# Main.net
KiCad netlist of a schematic drawn in Altium Designer
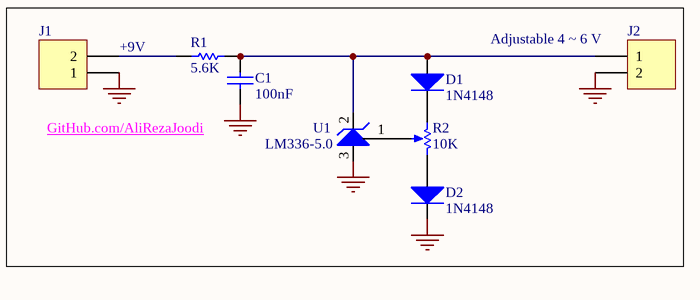
[diagram p0: Main.SchDoc]

(export (version "E")
  (design (tool "Eeschema 10.0.6"))
  (components
    (comp (ref "C1")
      (value "100nF")
      (footprint "CAPNTO2.54-3.05x1.78A")
      (description "Capacitor")
      (fields
        (field (name "MANUFACTURER") "Generic Components")
        (field (name "Comment") "Cap")
        (field (name "PUBLISHER") "Altium Limited")
      )
      (libsource (lib "Miscellaneous Devices") (part "Cap"))
    )
    (comp (ref "D1")
      (value "1N4148")
      (footprint "DIODE0.4_Glass")
      (description "Default Diode")
      (fields (field (name "MANUFACTURER") "Generic Components") (field (name "PUBLISHER") "Altium Limited"))
      (libsource (lib "Miscellaneous Devices") (part "Diode"))
    )
    (comp (ref "D2")
      (value "1N4148")
      (footprint "DIODE0.4_Glass")
      (description "Default Diode")
      (fields (field (name "MANUFACTURER") "Generic Components") (field (name "PUBLISHER") "Altium Limited"))
      (libsource (lib "Miscellaneous Devices") (part "Diode"))
    )
    (comp (ref "J1")
      (value "2PIN")
      (footprint "HDR1X2")
      (description "Header, 2-Pin")
      (fields (field (name "MANUFACTURER") "Generic Components") (field (name "PUBLISHER") "Altium Limited"))
      (libsource (lib "Miscellaneous Connectors") (part "Header 2"))
    )
    (comp (ref "J2")
      (value "2PIN")
      (footprint "HDR1X2")
      (description "Header, 2-Pin")
      (fields (field (name "MANUFACTURER") "Generic Components") (field (name "PUBLISHER") "Altium Limited"))
      (libsource (lib "") (part "Header 2_1"))
    )
    (comp (ref "R1")
      (value "5.6K")
      (footprint "AXIAL-0.4")
      (description "Resistor")
      (fields (field (name "Comment") "Res1") (field (name "PUBLISHER") "Altium Limited"))
      (libsource (lib "Miscellaneous Devices") (part "Res1"))
    )
    (comp (ref "R2")
      (value "10K")
      (footprint "VR4_")
      (description "Potentiometer")
      (fields
        (field (name "MANUFACTURER") "Generic Components")
        (field (name "Comment") "POT")
        (field (name "PUBLISHER") "Altium Limited")
      )
      (libsource (lib "my Libraries") (part "RPot1"))
    )
    (comp (ref "U1")
      (value "LM336-5.0")
      (footprint "TO92C")
      (description "Programmable Shunt Regulator")
      (libsource (lib "my Libraries") (part "LM336"))
    )
  )
  (nets
    (net (code "1") (name "GND") (class "Default")
      (node (ref "C1") (pin "2") (pinfunction "2_2") (pintype "passive"))
      (node (ref "D2") (pin "2") (pinfunction "K_2") (pintype "passive"))
      (node (ref "J1") (pin "1") (pinfunction "1_1") (pintype "passive"))
      (node (ref "J2") (pin "2") (pinfunction "2_2") (pintype "passive"))
      (node (ref "U1") (pin "3") (pinfunction "-_3") (pintype "passive"))
    )
    (net (code "2") (name "Net-(D1-A)") (class "Default")
      (node (ref "C1") (pin "1") (pinfunction "1_1") (pintype "passive"))
      (node (ref "D1") (pin "1") (pinfunction "A_1") (pintype "passive"))
      (node (ref "J2") (pin "1") (pinfunction "1_1") (pintype "passive"))
      (node (ref "R1") (pin "1") (pinfunction "1_1") (pintype "passive"))
      (node (ref "U1") (pin "2") (pinfunction "+_2") (pintype "passive"))
    )
    (net (code "3") (name "Net-(D1-K)") (class "Default")
      (node (ref "D1") (pin "2") (pinfunction "K_2") (pintype "passive"))
      (node (ref "R2") (pin "2") (pinfunction "BOT_2") (pintype "passive"))
    )
    (net (code "4") (name "Net-(D2-A)") (class "Default")
      (node (ref "D2") (pin "1") (pinfunction "A_1") (pintype "passive"))
      (node (ref "R2") (pin "1") (pinfunction "TOP_1") (pintype "passive"))
    )
    (net (code "5") (name "Net-(J1-Pad2)") (class "Default")
      (node (ref "J1") (pin "2") (pinfunction "2_2") (pintype "passive"))
      (node (ref "R1") (pin "2") (pinfunction "2_2") (pintype "passive"))
    )
    (net (code "6") (name "Net-(R2-TAP)") (class "Default")
      (node (ref "R2") (pin "3") (pinfunction "TAP_3") (pintype "passive"))
      (node (ref "U1") (pin "1") (pinfunction "Adj_1") (pintype "passive"))
    )
  )
)
